# Supply.net
KiCad netlist of a schematic drawn in Altium Designer
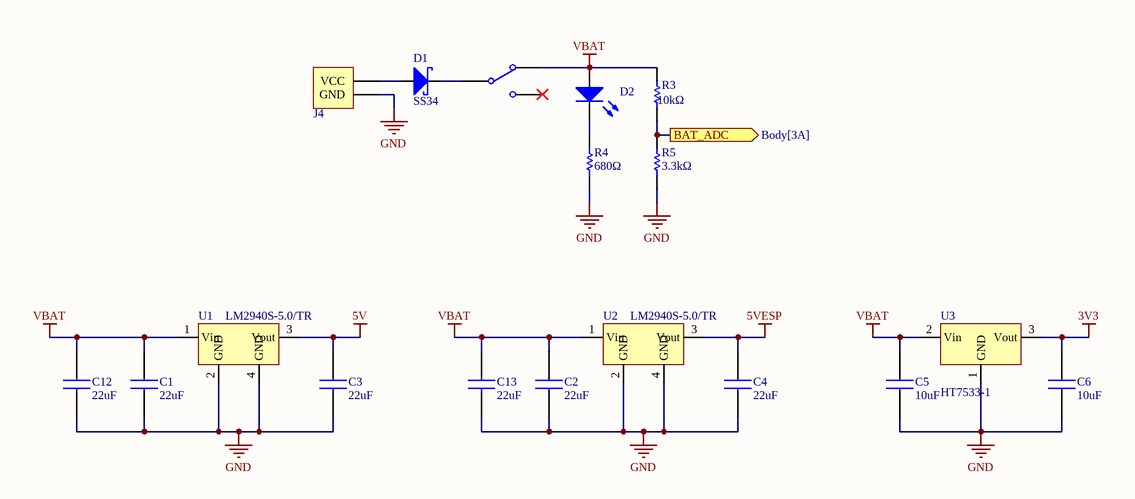
[diagram p0: Supply.SchDoc]

(export (version "E")
  (design (tool "Eeschema 10.0.6"))
  (components
    (comp (ref "C1")
      (value "22uF")
      (footprint "CAP0805")
      (description "25V 22uF X5R ±20% 0805 Multilayer Ceramic Capacitors MLCC - SMD/SMT ROHS")
      (fields (field (name "MANUFACTURER_PART_NUMBER") "CL21A226MAQNNNE"))
      (libsource (lib "StandartComponents") (part "CL21A226MAQNNNE"))
    )
    (comp (ref "C2")
      (value "22uF")
      (footprint "CAP0805")
      (description "25V 22uF X5R ±20% 0805 Multilayer Ceramic Capacitors MLCC - SMD/SMT ROHS")
      (fields (field (name "MANUFACTURER_PART_NUMBER") "CL21A226MAQNNNE"))
      (libsource (lib "StandartComponents") (part "CL21A226MAQNNNE"))
    )
    (comp (ref "C3")
      (value "22uF")
      (footprint "CAP0805")
      (description "25V 22uF X5R ±20% 0805 Multilayer Ceramic Capacitors MLCC - SMD/SMT ROHS")
      (fields (field (name "MANUFACTURER_PART_NUMBER") "CL21A226MAQNNNE"))
      (libsource (lib "StandartComponents") (part "CL21A226MAQNNNE"))
    )
    (comp (ref "C4")
      (value "22uF")
      (footprint "CAP0805")
      (description "25V 22uF X5R ±20% 0805 Multilayer Ceramic Capacitors MLCC - SMD/SMT ROHS")
      (fields (field (name "MANUFACTURER_PART_NUMBER") "CL21A226MAQNNNE"))
      (libsource (lib "StandartComponents") (part "CL21A226MAQNNNE"))
    )
    (comp (ref "C5")
      (value "10uF")
      (footprint "CAP0805")
      (description "50V 10uF X5R ±10% 0805 Multilayer Ceramic Capacitors MLCC - SMD/SMT ROHS")
      (fields
        (field (name "MANUFACTURER") "Murata Electronics")
        (field (name "PART NUMBER") "GRM21BR61H106KE43L")
      )
      (libsource (lib "StandartComponents") (part "GRM21BR61H106KE43L"))
    )
    (comp (ref "C6")
      (value "10uF")
      (footprint "CAP0805")
      (description "50V 10uF X5R ±10% 0805 Multilayer Ceramic Capacitors MLCC - SMD/SMT ROHS")
      (fields
        (field (name "MANUFACTURER") "Murata Electronics")
        (field (name "PART NUMBER") "GRM21BR61H106KE43L")
      )
      (libsource (lib "StandartComponents") (part "GRM21BR61H106KE43L"))
    )
    (comp (ref "C12")
      (value "22uF")
      (footprint "CAP0805")
      (description "25V 22uF X5R ±20% 0805 Multilayer Ceramic Capacitors MLCC - SMD/SMT ROHS")
      (fields (field (name "MANUFACTURER_PART_NUMBER") "CL21A226MAQNNNE"))
      (libsource (lib "StandartComponents") (part "CL21A226MAQNNNE"))
    )
    (comp (ref "C13")
      (value "22uF")
      (footprint "CAP0805")
      (description "25V 22uF X5R ±20% 0805 Multilayer Ceramic Capacitors MLCC - SMD/SMT ROHS")
      (fields (field (name "MANUFACTURER_PART_NUMBER") "CL21A226MAQNNNE"))
      (libsource (lib "StandartComponents") (part "CL21A226MAQNNNE"))
    )
    (comp (ref "D1")
      (value "SS34")
      (footprint "SMA_L4.3-W2.6-LS5.2-RD")
      (description "40V Independent Type 3A 550mV@3A SMA(DO-214AC) Schottky Diodes ROHS")
      (fields (field (name "MANUFACTURER") "MDD(Microdiode Semiconductor)"))
      (libsource (lib "StandartComponents") (part "SS34"))
    )
    (comp (ref "D2")
      (value "KT-0805G")
      (footprint "LED0805")
      (description "Emerald 0805 LED Indication - Discrete ROHS")
      (fields (field (name "MANUFACTURER") "Hubei KENTO Elec"))
      (libsource (lib "StandartComponents") (part "KT-0805G"))
    )
    (comp (ref "J4")
      (value "BATTERY")
      (footprint "XT30")
      (description "CONN BATTERY HORZ 2POS XT30")
      (fields
        (field (name "LIBRARY CONTROL - CHECKED FOOTPRINT") "Under review")
        (field (name "LIBRARY CONTROL - PERSON THAT CHECKED FOOTPRINT") "Lucas")
        (field (name "LIBRARY CONTROL - PERSON THAT CHECKED SCHEMATIC") "Lucas")
        (field (name "LIBRARY CONTROL - PERSON THAT DID THE LAST UPDATE FOOTPRINT") "Mateus(Dimas)")
        (field (name "LIBRARY CONTROL - PERSON THAT DID THE LAST UPDATE SCHEMATIC") "Mateus(Dimas)")
      )
      (libsource (lib "StandartComponents") (part "XT30"))
    )
    (comp (ref "R3")
      (value "10kΩ")
      (footprint "RES0805")
      (description "125mW Thick Film Resistors 150V ±100ppm/℃ ±1% 10kΩ 0805 Chip Resistor - Surface Mount ROHS")
      (fields (field (name "MANUFACTURER_PART_NUMBER") "0805W8F1002T5E"))
      (libsource (lib "StandartComponents") (part "0805W8F1002T5E"))
    )
    (comp (ref "R4")
      (value "680Ω")
      (footprint "RES0805")
      (description "125mW Thick Film Resistors 150V ±100ppm/℃ ±1% 680Ω 0805 Chip Resistor - Surface Mount ROHS")
      (fields (field (name "PART NUMBER") "0805W8F6800T5E"))
      (libsource (lib "StandartComponents") (part "0805W8F6800T5E"))
    )
    (comp (ref "R5")
      (value "3.3kΩ")
      (footprint "RES0805")
      (description "125mW Thick Film Resistors 150V ±100ppm/℃ ±1% 3.3kΩ 0805 Chip Resistor - Surface Mount ROHS")
      (fields (field (name "MANUFACTURER_PART_NUMBER") "0805W8F3301T5E"))
      (libsource (lib "StandartComponents") (part "0805W8F3301T5E"))
    )
    (comp (ref "SW1")
      (value "SS12D10G4 071")
      (footprint "SW-TH_SHOU-HAN_SS12D10G4")
      (fields (field (name "MANUFACTURER") "SHOU HAN(首韩)"))
      (libsource (lib "StandartComponents") (part "SS12D10G4 071"))
    )
    (comp (ref "U1")
      (value "LM2940S-5.0/TR")
      (footprint "TO-263-3_L8.6-W10.2-P2.54-LS14.4-BR")
      (fields (field (name "MANUFACTURER") "HGSEMI"))
      (libsource (lib "MainComponents") (part "LM2940S-5.0/TR"))
    )
    (comp (ref "U2")
      (value "LM2940S-5.0/TR")
      (footprint "TO-263-3_L8.6-W10.2-P2.54-LS14.4-BR")
      (fields (field (name "MANUFACTURER") "HGSEMI"))
      (libsource (lib "MainComponents") (part "LM2940S-5.0/TR"))
    )
    (comp (ref "U3")
      (value "HT7533-1")
      (footprint "SOT-89-3_L4.5-W2.5-P1.50-LS4.2-BR")
      (fields (field (name "MANUFACTURER") "Holtek Semicon"))
      (libsource (lib "MainComponents") (part "HT7533-1"))
    )
  )
  (nets
    (net (code "1") (name "/BAT_ADC") (class "Default")
      (node (ref "R3") (pin "1") (pinfunction "1_1") (pintype "passive"))
      (node (ref "R5") (pin "2") (pinfunction "2_2") (pintype "passive"))
    )
    (net (code "2") (name "3V3") (class "Default")
      (node (ref "C6") (pin "2") (pinfunction "2_2") (pintype "passive"))
      (node (ref "U3") (pin "3") (pinfunction "Vout_3") (pintype "power_in"))
    )
    (net (code "3") (name "5V") (class "Default")
      (node (ref "C3") (pin "2") (pinfunction "2_2") (pintype "passive"))
      (node (ref "U1") (pin "3") (pinfunction "Vout_3") (pintype "power_in"))
    )
    (net (code "4") (name "5VESP") (class "Default")
      (node (ref "C4") (pin "2") (pinfunction "2_2") (pintype "passive"))
      (node (ref "U2") (pin "3") (pinfunction "Vout_3") (pintype "power_in"))
    )
    (net (code "5") (name "GND") (class "Default")
      (node (ref "C1") (pin "1") (pinfunction "1_1") (pintype "passive"))
      (node (ref "C12") (pin "1") (pinfunction "1_1") (pintype "passive"))
      (node (ref "C13") (pin "1") (pinfunction "1_1") (pintype "passive"))
      (node (ref "C2") (pin "1") (pinfunction "1_1") (pintype "passive"))
      (node (ref "C3") (pin "1") (pinfunction "1_1") (pintype "passive"))
      (node (ref "C4") (pin "1") (pinfunction "1_1") (pintype "passive"))
      (node (ref "C5") (pin "1") (pinfunction "1_1") (pintype "passive"))
      (node (ref "C6") (pin "1") (pinfunction "1_1") (pintype "passive"))
      (node (ref "J4") (pin "2") (pinfunction "GND_2") (pintype "passive"))
      (node (ref "R4") (pin "1") (pinfunction "1_1") (pintype "passive"))
      (node (ref "R5") (pin "1") (pinfunction "1_1") (pintype "passive"))
      (node (ref "U1") (pin "2") (pinfunction "GND_2") (pintype "power_in"))
      (node (ref "U1") (pin "4") (pinfunction "GND_4") (pintype "power_in"))
      (node (ref "U2") (pin "2") (pinfunction "GND_2") (pintype "power_in"))
      (node (ref "U2") (pin "4") (pinfunction "GND_4") (pintype "power_in"))
      (node (ref "U3") (pin "1") (pinfunction "GND_1") (pintype "power_in"))
    )
    (net (code "6") (name "Net-(D2-PadK)") (class "Default")
      (node (ref "D2") (pin "K") (pinfunction "K_K") (pintype "passive"))
      (node (ref "R4") (pin "2") (pinfunction "2_2") (pintype "passive"))
    )
    (net (code "7") (name "Net-(J4-VCC)") (class "Default")
      (node (ref "D1") (pin "A") (pinfunction "A_A") (pintype "passive"))
      (node (ref "J4") (pin "1") (pinfunction "VCC_1") (pintype "passive"))
    )
    (net (code "8") (name "Net-(SW1-COMMON)") (class "Default")
      (node (ref "D1") (pin "C") (pinfunction "C_C") (pintype "passive"))
      (node (ref "SW1") (pin "2") (pinfunction "COMMON_2") (pintype "passive"))
    )
    (net (code "9") (name "VBAT") (class "Default")
      (node (ref "C1") (pin "2") (pinfunction "2_2") (pintype "passive"))
      (node (ref "C12") (pin "2") (pinfunction "2_2") (pintype "passive"))
      (node (ref "C13") (pin "2") (pinfunction "2_2") (pintype "passive"))
      (node (ref "C2") (pin "2") (pinfunction "2_2") (pintype "passive"))
      (node (ref "C5") (pin "2") (pinfunction "2_2") (pintype "passive"))
      (node (ref "D2") (pin "A") (pinfunction "A_A") (pintype "passive"))
      (node (ref "R3") (pin "2") (pinfunction "2_2") (pintype "passive"))
      (node (ref "SW1") (pin "1") (pinfunction "1_1") (pintype "passive"))
      (node (ref "U1") (pin "1") (pinfunction "Vin_1") (pintype "power_in"))
      (node (ref "U2") (pin "1") (pinfunction "Vin_1") (pintype "power_in"))
      (node (ref "U3") (pin "2") (pinfunction "Vin_2") (pintype "power_in"))
    )
    (net (code "10") (name "unconnected-(SW1-NO-Pad3)") (class "Default")
      (node (ref "SW1") (pin "3") (pinfunction "NO_3") (pintype "passive+no_connect"))
    )
  )
)
